# CAN_Communication.net
KiCad netlist of a schematic drawn in Altium Designer
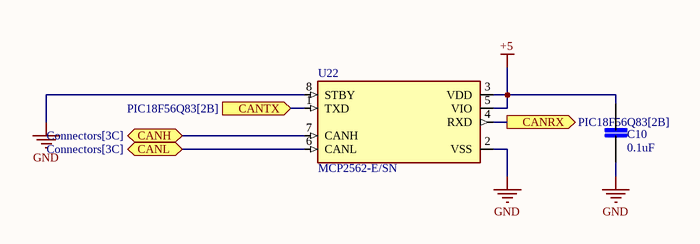
[diagram p0: CAN Communication.SchDoc]

(export (version "E")
  (design (tool "Eeschema 10.0.6"))
  (components
    (comp (ref "C10")
      (value "0.1uF")
      (footprint "0805")
      (fields (field (name "MP") "LD051A121KAB2A") (field (name "MF") "AVX"))
      (libsource (lib "Capacitors SMD") (part "0805_Capacitor"))
    )
    (comp (ref "U22")
      (value "MCP2562-E/SN")
      (footprint "Transceiver CAN:MCP2562-E/SN")
      (description "1/1 Transceiver Half CANbus 8-SOIC")
      (fields (field (name "MF") "Microchip"))
      (libsource (lib "Transceiver CAN") (part "MCP2562-E/SN"))
    )
  )
  (nets
    (net (code "1") (name "+5") (class "Default")
      (node (ref "C10") (pin "2") (pinfunction "2_2") (pintype "passive"))
      (node (ref "U22") (pin "3") (pinfunction "VDD_3") (pintype "power_in"))
      (node (ref "U22") (pin "5") (pinfunction "VIO_5") (pintype "power_in"))
    )
    (net (code "2") (name "/CANH") (class "Default")
      (node (ref "U22") (pin "7") (pinfunction "CANH_7") (pintype "input"))
    )
    (net (code "3") (name "/CANL") (class "Default")
      (node (ref "U22") (pin "6") (pinfunction "CANL_6") (pintype "input"))
    )
    (net (code "4") (name "/CANRX") (class "Default")
      (node (ref "U22") (pin "4") (pinfunction "RXD_4") (pintype "output"))
    )
    (net (code "5") (name "/CANTX") (class "Default")
      (node (ref "U22") (pin "1") (pinfunction "TXD_1") (pintype "input"))
    )
    (net (code "6") (name "GND") (class "Default")
      (node (ref "C10") (pin "1") (pinfunction "1_1") (pintype "passive"))
      (node (ref "U22") (pin "2") (pinfunction "VSS_2") (pintype "power_in"))
      (node (ref "U22") (pin "8") (pinfunction "STBY_8") (pintype "input"))
    )
  )
)
